# Synthesizer.net
KiCad netlist of a schematic drawn in Altium Designer
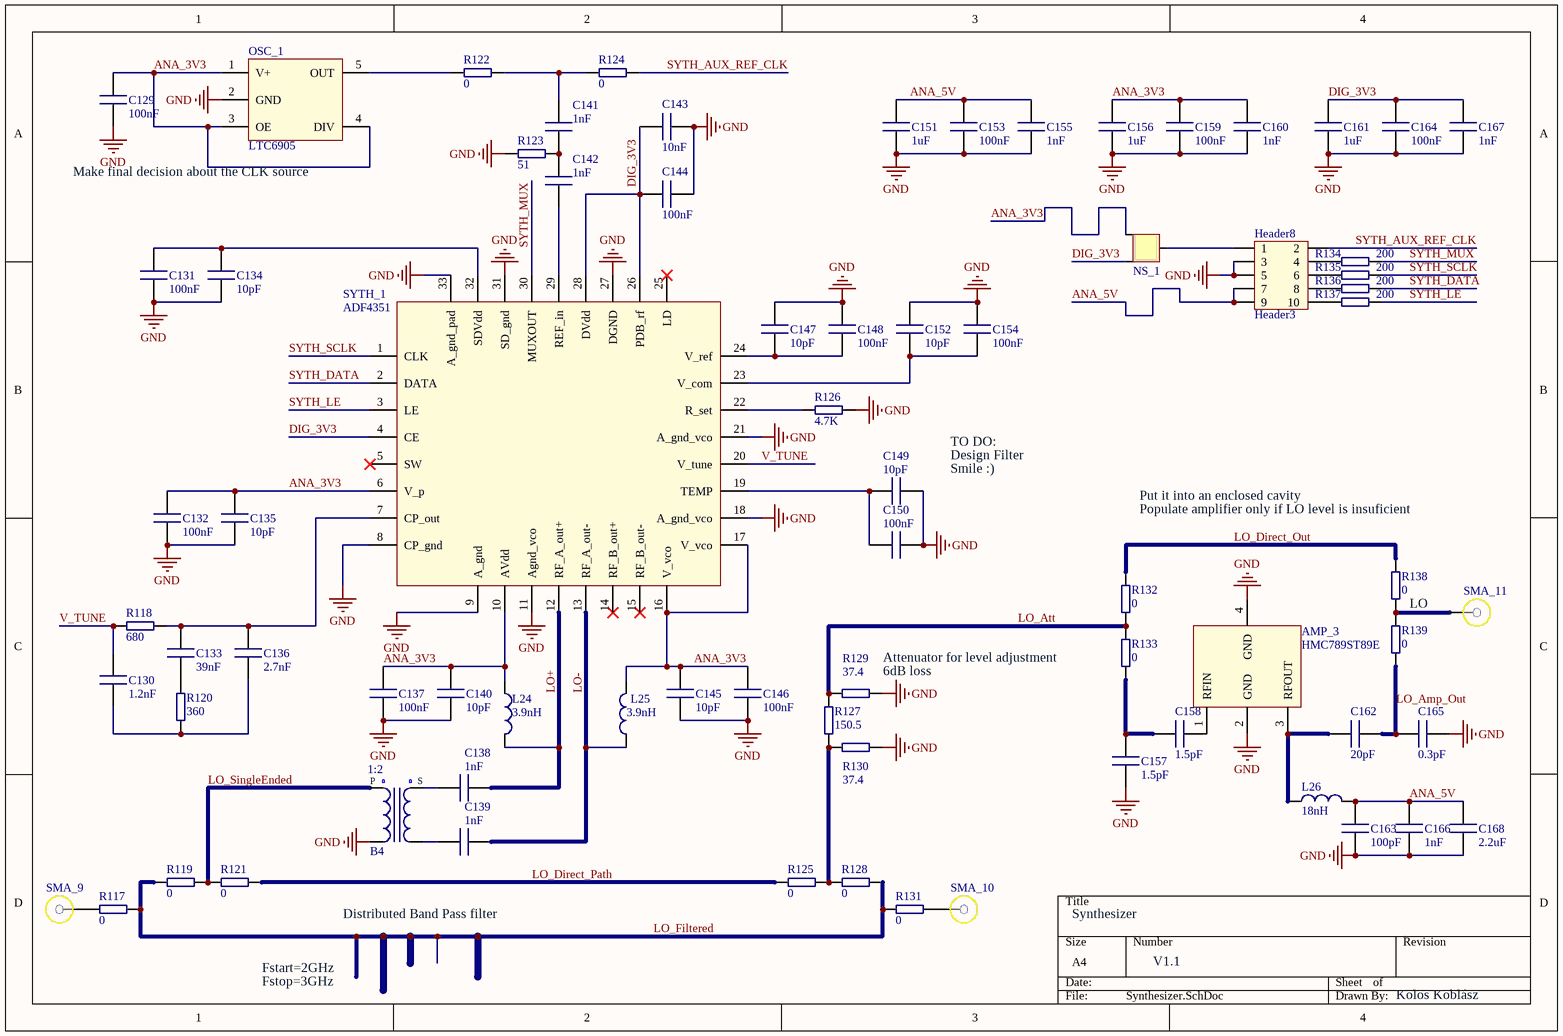
[diagram p0: Synthesizer.SchDoc]

(export (version "E")
  (design (tool "Eeschema 10.0.6"))
  (components
    (comp (ref "AMP_3")
      (value "HMC789ST89E")
      (description "Gain Block MMIC")
      (fields (field (name "MANUFACTURER") "Analog Devices"))
      (libsource (lib "RadioProjectSchLib") (part "HMC789ST89E"))
    )
    (comp (ref "B4")
      (value "Balun")
      (footprint "BALUN_CHIP")
      (description "SMD Balun")
      (fields
        (field (name "IMPEDANCETRANSFORMATION P : S") "1:2")
        (field (name "MANUFACTURER") "TDK")
        (field (name "PARTNUMBER") "HHM1918A2")
      )
      (libsource (lib "RadioProjectSchLib") (part "Balun4"))
    )
    (comp (ref "C129")
      (value "100nF")
      (footprint "0805 SMD Passive")
      (description "SMD Capacitor")
      (fields (field (name "Comment") "Cap1"))
      (libsource (lib "RadioProjectSchLib") (part "Cap1"))
    )
    (comp (ref "C130")
      (value "1.2nF")
      (footprint "0805 SMD Passive")
      (description "SMD Capacitor")
      (fields (field (name "Comment") "Cap1"))
      (libsource (lib "RadioProjectSchLib") (part "Cap1"))
    )
    (comp (ref "C131")
      (value "100nF")
      (footprint "0805 SMD Passive")
      (description "SMD Capacitor")
      (fields (field (name "Comment") "Cap1"))
      (libsource (lib "RadioProjectSchLib") (part "Cap1"))
    )
    (comp (ref "C132")
      (value "100nF")
      (footprint "0805 SMD Passive")
      (description "SMD Capacitor")
      (fields (field (name "Comment") "Cap1"))
      (libsource (lib "RadioProjectSchLib") (part "Cap1"))
    )
    (comp (ref "C133")
      (value "39nF")
      (footprint "0805 SMD Passive")
      (description "SMD Capacitor")
      (fields (field (name "Comment") "Cap1"))
      (libsource (lib "RadioProjectSchLib") (part "Cap1"))
    )
    (comp (ref "C134")
      (value "10pF")
      (footprint "0805 SMD Passive")
      (description "SMD Capacitor")
      (fields (field (name "Comment") "Cap1"))
      (libsource (lib "RadioProjectSchLib") (part "Cap1"))
    )
    (comp (ref "C135")
      (value "10pF")
      (footprint "0805 SMD Passive")
      (description "SMD Capacitor")
      (fields (field (name "Comment") "Cap1"))
      (libsource (lib "RadioProjectSchLib") (part "Cap1"))
    )
    (comp (ref "C136")
      (value "2.7nF")
      (footprint "0805 SMD Passive")
      (description "SMD Capacitor")
      (fields (field (name "Comment") "Cap1"))
      (libsource (lib "RadioProjectSchLib") (part "Cap1"))
    )
    (comp (ref "C137")
      (value "100nF")
      (footprint "0805 SMD Passive")
      (description "SMD Capacitor")
      (fields (field (name "Comment") "Cap1"))
      (libsource (lib "RadioProjectSchLib") (part "Cap1"))
    )
    (comp (ref "C138")
      (value "1nF")
      (footprint "0805 SMD Passive")
      (description "SMD Capacitor")
      (fields (field (name "Comment") "Cap1"))
      (libsource (lib "RadioProjectSchLib") (part "Cap1"))
    )
    (comp (ref "C139")
      (value "1nF")
      (footprint "0805 SMD Passive")
      (description "SMD Capacitor")
      (fields (field (name "Comment") "Cap1"))
      (libsource (lib "RadioProjectSchLib") (part "Cap1"))
    )
    (comp (ref "C140")
      (value "10pF")
      (footprint "0805 SMD Passive")
      (description "SMD Capacitor")
      (fields (field (name "Comment") "Cap1"))
      (libsource (lib "RadioProjectSchLib") (part "Cap1"))
    )
    (comp (ref "C141")
      (value "1nF")
      (footprint "0805 SMD Passive")
      (description "SMD Capacitor")
      (fields (field (name "Comment") "Cap1"))
      (libsource (lib "RadioProjectSchLib") (part "Cap1"))
    )
    (comp (ref "C142")
      (value "1nF")
      (footprint "0805 SMD Passive")
      (description "SMD Capacitor")
      (fields (field (name "Comment") "Cap1"))
      (libsource (lib "RadioProjectSchLib") (part "Cap1"))
    )
    (comp (ref "C143")
      (value "10nF")
      (footprint "0805 SMD Passive")
      (description "SMD Capacitor")
      (fields (field (name "Comment") "Cap1"))
      (libsource (lib "RadioProjectSchLib") (part "Cap1"))
    )
    (comp (ref "C144")
      (value "100nF")
      (footprint "0805 SMD Passive")
      (description "SMD Capacitor")
      (fields (field (name "Comment") "Cap1"))
      (libsource (lib "RadioProjectSchLib") (part "Cap1"))
    )
    (comp (ref "C145")
      (value "10pF")
      (footprint "0805 SMD Passive")
      (description "SMD Capacitor")
      (fields (field (name "Comment") "Cap1"))
      (libsource (lib "RadioProjectSchLib") (part "Cap1"))
    )
    (comp (ref "C146")
      (value "100nF")
      (footprint "0805 SMD Passive")
      (description "SMD Capacitor")
      (fields (field (name "Comment") "Cap1"))
      (libsource (lib "RadioProjectSchLib") (part "Cap1"))
    )
    (comp (ref "C147")
      (value "10pF")
      (footprint "0805 SMD Passive")
      (description "SMD Capacitor")
      (fields (field (name "Comment") "Cap1"))
      (libsource (lib "RadioProjectSchLib") (part "Cap1"))
    )
    (comp (ref "C148")
      (value "100nF")
      (footprint "0805 SMD Passive")
      (description "SMD Capacitor")
      (fields (field (name "Comment") "Cap1"))
      (libsource (lib "RadioProjectSchLib") (part "Cap1"))
    )
    (comp (ref "C149")
      (value "10pF")
      (footprint "0805 SMD Passive")
      (description "SMD Capacitor")
      (fields (field (name "Comment") "Cap1"))
      (libsource (lib "RadioProjectSchLib") (part "Cap1"))
    )
    (comp (ref "C150")
      (value "100nF")
      (footprint "0805 SMD Passive")
      (description "SMD Capacitor")
      (fields (field (name "Comment") "Cap1"))
      (libsource (lib "RadioProjectSchLib") (part "Cap1"))
    )
    (comp (ref "C151")
      (value "1uF")
      (footprint "0805 SMD Passive")
      (description "SMD Capacitor")
      (fields (field (name "Comment") "Cap1"))
      (libsource (lib "RadioProjectSchLib") (part "Cap1"))
    )
    (comp (ref "C152")
      (value "10pF")
      (footprint "0805 SMD Passive")
      (description "SMD Capacitor")
      (fields (field (name "Comment") "Cap1"))
      (libsource (lib "RadioProjectSchLib") (part "Cap1"))
    )
    (comp (ref "C153")
      (value "100nF")
      (footprint "0805 SMD Passive")
      (description "SMD Capacitor")
      (fields (field (name "Comment") "Cap1"))
      (libsource (lib "RadioProjectSchLib") (part "Cap1"))
    )
    (comp (ref "C154")
      (value "100nF")
      (footprint "0805 SMD Passive")
      (description "SMD Capacitor")
      (fields (field (name "Comment") "Cap1"))
      (libsource (lib "RadioProjectSchLib") (part "Cap1"))
    )
    (comp (ref "C155")
      (value "1nF")
      (footprint "0805 SMD Passive")
      (description "SMD Capacitor")
      (fields (field (name "Comment") "Cap1"))
      (libsource (lib "RadioProjectSchLib") (part "Cap1"))
    )
    (comp (ref "C156")
      (value "1uF")
      (footprint "0805 SMD Passive")
      (description "SMD Capacitor")
      (fields (field (name "Comment") "Cap1"))
      (libsource (lib "RadioProjectSchLib") (part "Cap1"))
    )
    (comp (ref "C157")
      (value "1.5pF")
      (footprint "0805 SMD Passive")
      (description "SMD Capacitor")
      (fields (field (name "Comment") "Cap1"))
      (libsource (lib "RadioProjectSchLib") (part "Cap1"))
    )
    (comp (ref "C158")
      (value "1.5pF")
      (footprint "0805 SMD Passive")
      (description "SMD Capacitor")
      (fields (field (name "Comment") "Cap1"))
      (libsource (lib "RadioProjectSchLib") (part "Cap1"))
    )
    (comp (ref "C159")
      (value "100nF")
      (footprint "0805 SMD Passive")
      (description "SMD Capacitor")
      (fields (field (name "Comment") "Cap1"))
      (libsource (lib "RadioProjectSchLib") (part "Cap1"))
    )
    (comp (ref "C160")
      (value "1nF")
      (footprint "0805 SMD Passive")
      (description "SMD Capacitor")
      (fields (field (name "Comment") "Cap1"))
      (libsource (lib "RadioProjectSchLib") (part "Cap1"))
    )
    (comp (ref "C161")
      (value "1uF")
      (footprint "0805 SMD Passive")
      (description "SMD Capacitor")
      (fields (field (name "Comment") "Cap1"))
      (libsource (lib "RadioProjectSchLib") (part "Cap1"))
    )
    (comp (ref "C162")
      (value "20pF")
      (footprint "0805 SMD Passive")
      (description "SMD Capacitor")
      (fields (field (name "Comment") "Cap1"))
      (libsource (lib "RadioProjectSchLib") (part "Cap1"))
    )
    (comp (ref "C163")
      (value "100pF")
      (footprint "0805 SMD Passive")
      (description "SMD Capacitor")
      (fields (field (name "Comment") "Cap1"))
      (libsource (lib "RadioProjectSchLib") (part "Cap1"))
    )
    (comp (ref "C164")
      (value "100nF")
      (footprint "0805 SMD Passive")
      (description "SMD Capacitor")
      (fields (field (name "Comment") "Cap1"))
      (libsource (lib "RadioProjectSchLib") (part "Cap1"))
    )
    (comp (ref "C165")
      (value "0.3pF")
      (footprint "0805 SMD Passive")
      (description "SMD Capacitor")
      (fields (field (name "Comment") "Cap1"))
      (libsource (lib "RadioProjectSchLib") (part "Cap1"))
    )
    (comp (ref "C166")
      (value "1nF")
      (footprint "0805 SMD Passive")
      (description "SMD Capacitor")
      (fields (field (name "Comment") "Cap1"))
      (libsource (lib "RadioProjectSchLib") (part "Cap1"))
    )
    (comp (ref "C167")
      (value "1nF")
      (footprint "0805 SMD Passive")
      (description "SMD Capacitor")
      (fields (field (name "Comment") "Cap1"))
      (libsource (lib "RadioProjectSchLib") (part "Cap1"))
    )
    (comp (ref "C168")
      (value "2.2uF")
      (footprint "0805 SMD Passive")
      (description "SMD Capacitor")
      (fields (field (name "Comment") "Cap1"))
      (libsource (lib "RadioProjectSchLib") (part "Cap1"))
    )
    (comp (ref "Header8")
      (value "Header3")
      (footprint "Header3")
      (description "10 pin DIL header")
      (libsource (lib "RadioProjectSchLib") (part "Header3"))
    )
    (comp (ref "L24")
      (value "3.9nH")
      (footprint "0805 SMD Passive")
      (description "SMD Inductor")
      (fields (field (name "Comment") "Inductor"))
      (libsource (lib "RadioProjectSchLib") (part "Ind1"))
    )
    (comp (ref "L25")
      (value "3.9nH")
      (footprint "0805 SMD Passive")
      (description "SMD Inductor")
      (fields (field (name "Comment") "Inductor"))
      (libsource (lib "RadioProjectSchLib") (part "Ind1"))
    )
    (comp (ref "L26")
      (value "18nH")
      (footprint "0805 SMD Passive")
      (description "SMD Inductor")
      (fields (field (name "Comment") "Inductor"))
      (libsource (lib "RadioProjectSchLib") (part "Ind1"))
    )
    (comp (ref "NS_1")
      (value "NetSplit")
      (footprint "NetSplit_2")
      (description "Net Split 2 to 1")
      (libsource (lib "RadioProjectSchLib") (part "NetSplit"))
    )
    (comp (ref "OSC_1")
      (value "LTC6905")
      (description "Fixed frequency oscillator")
      (fields (field (name "MANUFACTURER") "Analog Devices") (field (name "PARTNUMBER") "LTC6905-100"))
      (libsource (lib "RadioProjectSchLib") (part "LTC6905"))
    )
    (comp (ref "R117")
      (value "0")
      (footprint "0805 SMD Passive")
      (description "SMD Resistor")
      (fields (field (name "Comment") "Resistor"))
      (libsource (lib "RadioProjectSchLib") (part "Res1"))
    )
    (comp (ref "R118")
      (value "680")
      (footprint "0805 SMD Passive")
      (description "SMD Resistor")
      (fields (field (name "Comment") "Resistor"))
      (libsource (lib "RadioProjectSchLib") (part "Res1"))
    )
    (comp (ref "R119")
      (value "0")
      (footprint "0805 SMD Passive")
      (description "SMD Resistor")
      (fields (field (name "Comment") "Resistor"))
      (libsource (lib "RadioProjectSchLib") (part "Res1"))
    )
    (comp (ref "R120")
      (value "360")
      (footprint "0805 SMD Passive")
      (description "SMD Resistor")
      (fields (field (name "Comment") "Resistor"))
      (libsource (lib "RadioProjectSchLib") (part "Res1"))
    )
    (comp (ref "R121")
      (value "0")
      (footprint "0805 SMD Passive")
      (description "SMD Resistor")
      (fields (field (name "Comment") "Resistor"))
      (libsource (lib "RadioProjectSchLib") (part "Res1"))
    )
    (comp (ref "R122")
      (value "0")
      (footprint "0805 SMD Passive")
      (description "SMD Resistor")
      (fields (field (name "Comment") "Resistor"))
      (libsource (lib "RadioProjectSchLib") (part "Res1"))
    )
    (comp (ref "R123")
      (value "51")
      (footprint "0805 SMD Passive")
      (description "SMD Resistor")
      (fields (field (name "Comment") "Resistor"))
      (libsource (lib "RadioProjectSchLib") (part "Res1"))
    )
    (comp (ref "R124")
      (value "0")
      (footprint "0805 SMD Passive")
      (description "SMD Resistor")
      (fields (field (name "Comment") "Resistor"))
      (libsource (lib "RadioProjectSchLib") (part "Res1"))
    )
    (comp (ref "R125")
      (value "0")
      (footprint "0805 SMD Passive")
      (description "SMD Resistor")
      (fields (field (name "Comment") "Resistor"))
      (libsource (lib "RadioProjectSchLib") (part "Res1"))
    )
    (comp (ref "R126")
      (value "4.7K")
      (footprint "0805 SMD Passive")
      (description "SMD Resistor")
      (fields (field (name "Comment") "Resistor"))
      (libsource (lib "RadioProjectSchLib") (part "Res1"))
    )
    (comp (ref "R127")
      (value "150.5")
      (footprint "0805 SMD Passive")
      (description "SMD Resistor")
      (fields (field (name "Comment") "Resistor"))
      (libsource (lib "RadioProjectSchLib") (part "Res1"))
    )
    (comp (ref "R128")
      (value "0")
      (footprint "0805 SMD Passive")
      (description "SMD Resistor")
      (fields (field (name "Comment") "Resistor"))
      (libsource (lib "RadioProjectSchLib") (part "Res1"))
    )
    (comp (ref "R129")
      (value "37.4")
      (footprint "0805 SMD Passive")
      (description "SMD Resistor")
      (fields (field (name "Comment") "Resistor"))
      (libsource (lib "RadioProjectSchLib") (part "Res1"))
    )
    (comp (ref "R130")
      (value "37.4")
      (footprint "0805 SMD Passive")
      (description "SMD Resistor")
      (fields (field (name "Comment") "Resistor"))
      (libsource (lib "RadioProjectSchLib") (part "Res1"))
    )
    (comp (ref "R131")
      (value "0")
      (footprint "0805 SMD Passive")
      (description "SMD Resistor")
      (fields (field (name "Comment") "Resistor"))
      (libsource (lib "RadioProjectSchLib") (part "Res1"))
    )
    (comp (ref "R132")
      (value "0")
      (footprint "0805 SMD Passive")
      (description "SMD Resistor")
      (fields (field (name "Comment") "Resistor"))
      (libsource (lib "RadioProjectSchLib") (part "Res1"))
    )
    (comp (ref "R133")
      (value "0")
      (footprint "0805 SMD Passive")
      (description "SMD Resistor")
      (fields (field (name "Comment") "Resistor"))
      (libsource (lib "RadioProjectSchLib") (part "Res1"))
    )
    (comp (ref "R134")
      (value "200")
      (footprint "0805 SMD Passive")
      (description "SMD Resistor")
      (fields (field (name "Comment") "Resistor"))
      (libsource (lib "RadioProjectSchLib") (part "Res1"))
    )
    (comp (ref "R135")
      (value "200")
      (footprint "0805 SMD Passive")
      (description "SMD Resistor")
      (fields (field (name "Comment") "Resistor"))
      (libsource (lib "RadioProjectSchLib") (part "Res1"))
    )
    (comp (ref "R136")
      (value "200")
      (footprint "0805 SMD Passive")
      (description "SMD Resistor")
      (fields (field (name "Comment") "Resistor"))
      (libsource (lib "RadioProjectSchLib") (part "Res1"))
    )
    (comp (ref "R137")
      (value "200")
      (footprint "0805 SMD Passive")
      (description "SMD Resistor")
      (fields (field (name "Comment") "Resistor"))
      (libsource (lib "RadioProjectSchLib") (part "Res1"))
    )
    (comp (ref "R138")
      (value "0")
      (footprint "0805 SMD Passive")
      (description "SMD Resistor")
      (fields (field (name "Comment") "Resistor"))
      (libsource (lib "RadioProjectSchLib") (part "Res1"))
    )
    (comp (ref "R139")
      (value "0")
      (footprint "0805 SMD Passive")
      (description "SMD Resistor")
      (fields (field (name "Comment") "Resistor"))
      (libsource (lib "RadioProjectSchLib") (part "Res1"))
    )
    (comp (ref "SMA_9")
      (value "SMA1")
      (footprint "SMA Flange")
      (description "SMA Female")
      (libsource (lib "RadioProjectSchLib") (part "SMA1"))
    )
    (comp (ref "SMA_10")
      (value "SMA1")
      (footprint "SMA Flange")
      (description "SMA Female")
      (libsource (lib "RadioProjectSchLib") (part "SMA1"))
    )
    (comp (ref "SMA_11")
      (value "SMA1")
      (footprint "SMA Flange")
      (description "SMA Female")
      (libsource (lib "RadioProjectSchLib") (part "SMA1"))
    )
    (comp (ref "SYTH_1")
      (value "ADF4351")
      (footprint "LFCSP-32")
      (description "Sythesizer with integrated VCO")
      (fields (field (name "MANUFACTURER") "Analog Devices"))
      (libsource (lib "RadioProjectSchLib") (part "ADF4351"))
    )
  )
  (nets
    (net (code "1") (name "/ANA_3V3") (class "Default")
      (node (ref "C129") (pin "1") (pinfunction "*_1") (pintype "passive"))
      (node (ref "C132") (pin "1") (pinfunction "*_1") (pintype "passive"))
      (node (ref "C135") (pin "1") (pinfunction "*_1") (pintype "passive"))
      (node (ref "C137") (pin "1") (pinfunction "*_1") (pintype "passive"))
      (node (ref "C140") (pin "1") (pinfunction "*_1") (pintype "passive"))
      (node (ref "C145") (pin "1") (pinfunction "*_1") (pintype "passive"))
      (node (ref "C146") (pin "1") (pinfunction "*_1") (pintype "passive"))
      (node (ref "C156") (pin "2") (pinfunction "*_2") (pintype "passive"))
      (node (ref "C159") (pin "2") (pinfunction "*_2") (pintype "passive"))
      (node (ref "C160") (pin "2") (pinfunction "*_2") (pintype "passive"))
      (node (ref "L24") (pin "1") (pinfunction "*_1") (pintype "passive"))
      (node (ref "L25") (pin "2") (pinfunction "*_2") (pintype "passive"))
      (node (ref "NS_1") (pin "0") (pinfunction "0_0") (pintype "passive"))
      (node (ref "OSC_1") (pin "1") (pinfunction "V+_1") (pintype "passive"))
      (node (ref "OSC_1") (pin "3") (pinfunction "OE_3") (pintype "passive"))
      (node (ref "OSC_1") (pin "4") (pinfunction "DIV_4") (pintype "passive"))
      (node (ref "SYTH_1") (pin "10") (pinfunction "AVdd_10") (pintype "passive"))
      (node (ref "SYTH_1") (pin "16") (pinfunction "V_vco_16") (pintype "passive"))
      (node (ref "SYTH_1") (pin "17") (pinfunction "V_vco_17") (pintype "passive"))
      (node (ref "SYTH_1") (pin "6") (pinfunction "V_p_6") (pintype "passive"))
    )
    (net (code "2") (name "/ANA_5V") (class "Default")
      (node (ref "C151") (pin "2") (pinfunction "*_2") (pintype "passive"))
      (node (ref "C153") (pin "2") (pinfunction "*_2") (pintype "passive"))
      (node (ref "C155") (pin "2") (pinfunction "*_2") (pintype "passive"))
      (node (ref "C163") (pin "1") (pinfunction "*_1") (pintype "passive"))
      (node (ref "C166") (pin "1") (pinfunction "*_1") (pintype "passive"))
      (node (ref "C168") (pin "1") (pinfunction "*_1") (pintype "passive"))
      (node (ref "Header8") (pin "7") (pinfunction "7_7") (pintype "passive"))
      (node (ref "Header8") (pin "9") (pinfunction "9_9") (pintype "passive"))
      (node (ref "L26") (pin "2") (pinfunction "*_2") (pintype "passive"))
    )
    (net (code "3") (name "/DIG_3V3") (class "Default")
      (node (ref "C143") (pin "1") (pinfunction "*_1") (pintype "passive"))
      (node (ref "C144") (pin "1") (pinfunction "*_1") (pintype "passive"))
      (node (ref "C161") (pin "2") (pinfunction "*_2") (pintype "passive"))
      (node (ref "C164") (pin "2") (pinfunction "*_2") (pintype "passive"))
      (node (ref "C167") (pin "2") (pinfunction "*_2") (pintype "passive"))
      (node (ref "NS_1") (pin "0") (pinfunction "0_0") (pintype "passive"))
      (node (ref "SYTH_1") (pin "26") (pinfunction "PDB_rf_26") (pintype "passive"))
      (node (ref "SYTH_1") (pin "28") (pinfunction "DVdd_28") (pintype "passive"))
      (node (ref "SYTH_1") (pin "4") (pinfunction "CE_4") (pintype "passive"))
    )
    (net (code "4") (name "/LO+") (class "Default")
      (node (ref "C138") (pin "2") (pinfunction "*_2") (pintype "passive"))
      (node (ref "L24") (pin "2") (pinfunction "*_2") (pintype "passive"))
      (node (ref "SYTH_1") (pin "12") (pinfunction "RF_A_out+_12") (pintype "passive"))
    )
    (net (code "5") (name "/LO-") (class "Default")
      (node (ref "C139") (pin "2") (pinfunction "*_2") (pintype "passive"))
      (node (ref "L25") (pin "1") (pinfunction "*_1") (pintype "passive"))
      (node (ref "SYTH_1") (pin "13") (pinfunction "RF_A_out-_13") (pintype "passive"))
    )
    (net (code "6") (name "/LO_Amp_Out") (class "Default")
      (node (ref "C162") (pin "2") (pinfunction "*_2") (pintype "passive"))
      (node (ref "C165") (pin "1") (pinfunction "*_1") (pintype "passive"))
      (node (ref "R139") (pin "1") (pinfunction "*_1") (pintype "passive"))
    )
    (net (code "7") (name "/LO_Att") (class "Default")
      (node (ref "R127") (pin "1") (pinfunction "*_1") (pintype "passive"))
      (node (ref "R129") (pin "1") (pinfunction "*_1") (pintype "passive"))
      (node (ref "R132") (pin "1") (pinfunction "*_1") (pintype "passive"))
      (node (ref "R133") (pin "2") (pinfunction "*_2") (pintype "passive"))
    )
    (net (code "8") (name "/LO_Direct_Out") (class "Default")
      (node (ref "R132") (pin "2") (pinfunction "*_2") (pintype "passive"))
      (node (ref "R138") (pin "2") (pinfunction "*_2") (pintype "passive"))
    )
    (net (code "9") (name "/LO_Direct_Path") (class "Default")
      (node (ref "R121") (pin "2") (pinfunction "*_2") (pintype "passive"))
      (node (ref "R125") (pin "1") (pinfunction "*_1") (pintype "passive"))
    )
    (net (code "10") (name "/LO_Filtered") (class "Default")
      (node (ref "R117") (pin "2") (pinfunction "*_2") (pintype "passive"))
      (node (ref "R119") (pin "1") (pinfunction "*_1") (pintype "passive"))
      (node (ref "R128") (pin "2") (pinfunction "*_2") (pintype "passive"))
      (node (ref "R131") (pin "1") (pinfunction "*_1") (pintype "passive"))
    )
    (net (code "11") (name "/LO_SingleEnded") (class "Default")
      (node (ref "B4") (pin "2") (pinfunction "2_2") (pintype "passive"))
      (node (ref "R119") (pin "2") (pinfunction "*_2") (pintype "passive"))
      (node (ref "R121") (pin "1") (pinfunction "*_1") (pintype "passive"))
    )
    (net (code "12") (name "/SYTH_AUX_REF_CLK") (class "Default")
      (node (ref "Header8") (pin "2") (pinfunction "2_2") (pintype "passive"))
      (node (ref "R124") (pin "2") (pinfunction "*_2") (pintype "passive"))
    )
    (net (code "13") (name "/SYTH_DATA") (class "Default")
      (node (ref "R136") (pin "1") (pinfunction "*_1") (pintype "passive"))
      (node (ref "SYTH_1") (pin "2") (pinfunction "DATA_2") (pintype "passive"))
    )
    (net (code "14") (name "/SYTH_LE") (class "Default")
      (node (ref "R137") (pin "1") (pinfunction "*_1") (pintype "passive"))
      (node (ref "SYTH_1") (pin "3") (pinfunction "LE_3") (pintype "passive"))
    )
    (net (code "15") (name "/SYTH_MUX") (class "Default")
      (node (ref "R134") (pin "1") (pinfunction "*_1") (pintype "passive"))
      (node (ref "SYTH_1") (pin "30") (pinfunction "MUXOUT_30") (pintype "passive"))
    )
    (net (code "16") (name "/SYTH_SCLK") (class "Default")
      (node (ref "R135") (pin "1") (pinfunction "*_1") (pintype "passive"))
      (node (ref "SYTH_1") (pin "1") (pinfunction "CLK_1") (pintype "passive"))
    )
    (net (code "17") (name "/V_TUNE") (class "Default")
      (node (ref "C130") (pin "1") (pinfunction "*_1") (pintype "passive"))
      (node (ref "R118") (pin "2") (pinfunction "*_2") (pintype "passive"))
      (node (ref "SYTH_1") (pin "20") (pinfunction "V_tune_20") (pintype "passive"))
    )
    (net (code "18") (name "GND") (class "Default")
      (node (ref "AMP_3") (pin "2") (pinfunction "GND_2") (pintype "passive"))
      (node (ref "AMP_3") (pin "4") (pinfunction "GND_4") (pintype "passive"))
      (node (ref "B4") (pin "4") (pinfunction "4_4") (pintype "passive"))
      (node (ref "C129") (pin "2") (pinfunction "*_2") (pintype "passive"))
      (node (ref "C131") (pin "2") (pinfunction "*_2") (pintype "passive"))
      (node (ref "C132") (pin "2") (pinfunction "*_2") (pintype "passive"))
      (node (ref "C134") (pin "2") (pinfunction "*_2") (pintype "passive"))
      (node (ref "C135") (pin "2") (pinfunction "*_2") (pintype "passive"))
      (node (ref "C137") (pin "2") (pinfunction "*_2") (pintype "passive"))
      (node (ref "C140") (pin "2") (pinfunction "*_2") (pintype "passive"))
      (node (ref "C143") (pin "2") (pinfunction "*_2") (pintype "passive"))
      (node (ref "C144") (pin "2") (pinfunction "*_2") (pintype "passive"))
      (node (ref "C145") (pin "2") (pinfunction "*_2") (pintype "passive"))
      (node (ref "C146") (pin "2") (pinfunction "*_2") (pintype "passive"))
      (node (ref "C147") (pin "2") (pinfunction "*_2") (pintype "passive"))
      (node (ref "C148") (pin "2") (pinfunction "*_2") (pintype "passive"))
      (node (ref "C149") (pin "2") (pinfunction "*_2") (pintype "passive"))
      (node (ref "C150") (pin "2") (pinfunction "*_2") (pintype "passive"))
      (node (ref "C151") (pin "1") (pinfunction "*_1") (pintype "passive"))
      (node (ref "C152") (pin "2") (pinfunction "*_2") (pintype "passive"))
      (node (ref "C153") (pin "1") (pinfunction "*_1") (pintype "passive"))
      (node (ref "C154") (pin "2") (pinfunction "*_2") (pintype "passive"))
      (node (ref "C155") (pin "1") (pinfunction "*_1") (pintype "passive"))
      (node (ref "C156") (pin "1") (pinfunction "*_1") (pintype "passive"))
      (node (ref "C157") (pin "1") (pinfunction "*_1") (pintype "passive"))
      (node (ref "C159") (pin "1") (pinfunction "*_1") (pintype "passive"))
      (node (ref "C160") (pin "1") (pinfunction "*_1") (pintype "passive"))
      (node (ref "C161") (pin "1") (pinfunction "*_1") (pintype "passive"))
      (node (ref "C163") (pin "2") (pinfunction "*_2") (pintype "passive"))
      (node (ref "C164") (pin "1") (pinfunction "*_1") (pintype "passive"))
      (node (ref "C165") (pin "2") (pinfunction "*_2") (pintype "passive"))
      (node (ref "C166") (pin "2") (pinfunction "*_2") (pintype "passive"))
      (node (ref "C167") (pin "1") (pinfunction "*_1") (pintype "passive"))
      (node (ref "C168") (pin "2") (pinfunction "*_2") (pintype "passive"))
      (node (ref "Header8") (pin "3") (pinfunction "3_3") (pintype "passive"))
      (node (ref "Header8") (pin "5") (pinfunction "5_5") (pintype "passive"))
      (node (ref "OSC_1") (pin "2") (pinfunction "GND_2") (pintype "passive"))
      (node (ref "R123") (pin "1") (pinfunction "*_1") (pintype "passive"))
      (node (ref "R126") (pin "2") (pinfunction "*_2") (pintype "passive"))
      (node (ref "R129") (pin "2") (pinfunction "*_2") (pintype "passive"))
      (node (ref "R130") (pin "2") (pinfunction "*_2") (pintype "passive"))
      (node (ref "SYTH_1") (pin "11") (pinfunction "Agnd_vco_11") (pintype "passive"))
      (node (ref "SYTH_1") (pin "18") (pinfunction "A_gnd_vco_18") (pintype "passive"))
      (node (ref "SYTH_1") (pin "21") (pinfunction "A_gnd_vco_21") (pintype "passive"))
      (node (ref "SYTH_1") (pin "27") (pinfunction "DGND_27") (pintype "passive"))
      (node (ref "SYTH_1") (pin "31") (pinfunction "SD_gnd_31") (pintype "passive"))
      (node (ref "SYTH_1") (pin "33") (pinfunction "A_gnd_pad_33") (pintype "passive"))
      (node (ref "SYTH_1") (pin "8") (pinfunction "CP_gnd_8") (pintype "passive"))
      (node (ref "SYTH_1") (pin "9") (pinfunction "A_gnd_9") (pintype "passive"))
    )
    (net (code "19") (name "Net-(AMP_3-RFIN)") (class "Default")
      (node (ref "AMP_3") (pin "1") (pinfunction "RFIN_1") (pintype "passive"))
      (node (ref "C158") (pin "2") (pinfunction "*_2") (pintype "passive"))
    )
    (net (code "20") (name "Net-(AMP_3-RFOUT)") (class "Default")
      (node (ref "AMP_3") (pin "3") (pinfunction "RFOUT_3") (pintype "passive"))
      (node (ref "C162") (pin "1") (pinfunction "*_1") (pintype "passive"))
      (node (ref "L26") (pin "1") (pinfunction "*_1") (pintype "passive"))
    )
    (net (code "21") (name "Net-(B4-Pad1)") (class "Default")
      (node (ref "B4") (pin "1") (pinfunction "1_1") (pintype "passive"))
      (node (ref "C138") (pin "1") (pinfunction "*_1") (pintype "passive"))
    )
    (net (code "22") (name "Net-(B4-Pad3)") (class "Default")
      (node (ref "B4") (pin "3") (pinfunction "3_3") (pintype "passive"))
      (node (ref "C139") (pin "1") (pinfunction "*_1") (pintype "passive"))
    )
    (net (code "23") (name "Net-(C130-*-Pad2)") (class "Default")
      (node (ref "C130") (pin "2") (pinfunction "*_2") (pintype "passive"))
      (node (ref "C136") (pin "2") (pinfunction "*_2") (pintype "passive"))
      (node (ref "R120") (pin "1") (pinfunction "*_1") (pintype "passive"))
    )
    (net (code "24") (name "Net-(C133-*-Pad2)") (class "Default")
      (node (ref "C133") (pin "2") (pinfunction "*_2") (pintype "passive"))
      (node (ref "R120") (pin "2") (pinfunction "*_2") (pintype "passive"))
    )
    (net (code "25") (name "Net-(C141-*-Pad1)") (class "Default")
      (node (ref "C141") (pin "1") (pinfunction "*_1") (pintype "passive"))
      (node (ref "R122") (pin "2") (pinfunction "*_2") (pintype "passive"))
      (node (ref "R124") (pin "1") (pinfunction "*_1") (pintype "passive"))
    )
    (net (code "26") (name "Net-(C141-*-Pad2)") (class "Default")
      (node (ref "C141") (pin "2") (pinfunction "*_2") (pintype "passive"))
      (node (ref "C142") (pin "1") (pinfunction "*_1") (pintype "passive"))
      (node (ref "R123") (pin "2") (pinfunction "*_2") (pintype "passive"))
    )
    (net (code "27") (name "Net-(C157-*-Pad2)") (class "Default")
      (node (ref "C157") (pin "2") (pinfunction "*_2") (pintype "passive"))
      (node (ref "C158") (pin "1") (pinfunction "*_1") (pintype "passive"))
      (node (ref "R133") (pin "1") (pinfunction "*_1") (pintype "passive"))
    )
    (net (code "28") (name "Net-(Header8-Pad1)") (class "Default")
      (node (ref "Header8") (pin "1") (pinfunction "1_1") (pintype "passive"))
      (node (ref "NS_1") (pin "0") (pinfunction "0_0") (pintype "passive"))
    )
    (net (code "29") (name "Net-(Header8-Pad4)") (class "Default")
      (node (ref "Header8") (pin "4") (pinfunction "4_4") (pintype "passive"))
      (node (ref "R134") (pin "2") (pinfunction "*_2") (pintype "passive"))
    )
    (net (code "30") (name "Net-(Header8-Pad6)") (class "Default")
      (node (ref "Header8") (pin "6") (pinfunction "6_6") (pintype "passive"))
      (node (ref "R135") (pin "2") (pinfunction "*_2") (pintype "passive"))
    )
    (net (code "31") (name "Net-(Header8-Pad8)") (class "Default")
      (node (ref "Header8") (pin "8") (pinfunction "8_8") (pintype "passive"))
      (node (ref "R136") (pin "2") (pinfunction "*_2") (pintype "passive"))
    )
    (net (code "32") (name "Net-(Header8-Pad10)") (class "Default")
      (node (ref "Header8") (pin "10") (pinfunction "10_10") (pintype "passive"))
      (node (ref "R137") (pin "2") (pinfunction "*_2") (pintype "passive"))
    )
    (net (code "33") (name "Net-(OSC_1-OUT)") (class "Default")
      (node (ref "OSC_1") (pin "5") (pinfunction "OUT_5") (pintype "passive"))
      (node (ref "R122") (pin "1") (pinfunction "*_1") (pintype "passive"))
    )
    (net (code "34") (name "Net-(R117-*-Pad1)") (class "Default")
      (node (ref "R117") (pin "1") (pinfunction "*_1") (pintype "passive"))
      (node (ref "SMA_9") (pin "1") (pinfunction "1_1") (pintype "passive"))
    )
    (net (code "35") (name "Net-(R125-*-Pad2)") (class "Default")
      (node (ref "R125") (pin "2") (pinfunction "*_2") (pintype "passive"))
      (node (ref "R127") (pin "2") (pinfunction "*_2") (pintype "passive"))
      (node (ref "R128") (pin "1") (pinfunction "*_1") (pintype "passive"))
      (node (ref "R130") (pin "1") (pinfunction "*_1") (pintype "passive"))
    )
    (net (code "36") (name "Net-(R131-*-Pad2)") (class "Default")
      (node (ref "R131") (pin "2") (pinfunction "*_2") (pintype "passive"))
      (node (ref "SMA_10") (pin "1") (pinfunction "1_1") (pintype "passive"))
    )
    (net (code "37") (name "Net-(R138-*-Pad1)") (class "Default")
      (node (ref "R138") (pin "1") (pinfunction "*_1") (pintype "passive"))
      (node (ref "R139") (pin "2") (pinfunction "*_2") (pintype "passive"))
      (node (ref "SMA_11") (pin "1") (pinfunction "1_1") (pintype "passive"))
    )
    (net (code "38") (name "Net-(SYTH_1-CP_out)") (class "Default")
      (node (ref "C133") (pin "1") (pinfunction "*_1") (pintype "passive"))
      (node (ref "C136") (pin "1") (pinfunction "*_1") (pintype "passive"))
      (node (ref "R118") (pin "1") (pinfunction "*_1") (pintype "passive"))
      (node (ref "SYTH_1") (pin "7") (pinfunction "CP_out_7") (pintype "passive"))
    )
    (net (code "39") (name "Net-(SYTH_1-REF_in)") (class "Default")
      (node (ref "C142") (pin "2") (pinfunction "*_2") (pintype "passive"))
      (node (ref "SYTH_1") (pin "29") (pinfunction "REF_in_29") (pintype "passive"))
    )
    (net (code "40") (name "Net-(SYTH_1-R_set)") (class "Default")
      (node (ref "R126") (pin "1") (pinfunction "*_1") (pintype "passive"))
      (node (ref "SYTH_1") (pin "22") (pinfunction "R_set_22") (pintype "passive"))
    )
    (net (code "41") (name "Net-(SYTH_1-SDVdd)") (class "Default")
      (node (ref "C131") (pin "1") (pinfunction "*_1") (pintype "passive"))
      (node (ref "C134") (pin "1") (pinfunction "*_1") (pintype "passive"))
      (node (ref "SYTH_1") (pin "32") (pinfunction "SDVdd_32") (pintype "passive"))
    )
    (net (code "42") (name "Net-(SYTH_1-TEMP)") (class "Default")
      (node (ref "C149") (pin "1") (pinfunction "*_1") (pintype "passive"))
      (node (ref "C150") (pin "1") (pinfunction "*_1") (pintype "passive"))
      (node (ref "SYTH_1") (pin "19") (pinfunction "TEMP_19") (pintype "passive"))
    )
    (net (code "43") (name "Net-(SYTH_1-V_com)") (class "Default")
      (node (ref "C152") (pin "1") (pinfunction "*_1") (pintype "passive"))
      (node (ref "C154") (pin "1") (pinfunction "*_1") (pintype "passive"))
      (node (ref "SYTH_1") (pin "23") (pinfunction "V_com_23") (pintype "passive"))
    )
    (net (code "44") (name "Net-(SYTH_1-V_ref)") (class "Default")
      (node (ref "C147") (pin "1") (pinfunction "*_1") (pintype "passive"))
      (node (ref "C148") (pin "1") (pinfunction "*_1") (pintype "passive"))
      (node (ref "SYTH_1") (pin "24") (pinfunction "V_ref_24") (pintype "passive"))
    )
    (net (code "45") (name "unconnected-(SYTH_1-LD-Pad25)") (class "Default")
      (node (ref "SYTH_1") (pin "25") (pinfunction "LD_25") (pintype "passive+no_connect"))
    )
    (net (code "46") (name "unconnected-(SYTH_1-RF_B_out+-Pad14)") (class "Default")
      (node (ref "SYTH_1") (pin "14") (pinfunction "RF_B_out+_14") (pintype "passive+no_connect"))
    )
    (net (code "47") (name "unconnected-(SYTH_1-RF_B_out--Pad15)") (class "Default")
      (node (ref "SYTH_1") (pin "15") (pinfunction "RF_B_out-_15") (pintype "passive+no_connect"))
    )
    (net (code "48") (name "unconnected-(SYTH_1-SW-Pad5)") (class "Default")
      (node (ref "SYTH_1") (pin "5") (pinfunction "SW_5") (pintype "passive+no_connect"))
    )
  )
)
